# breakout4hold.net
KiCad netlist of a schematic drawn in EAGLE
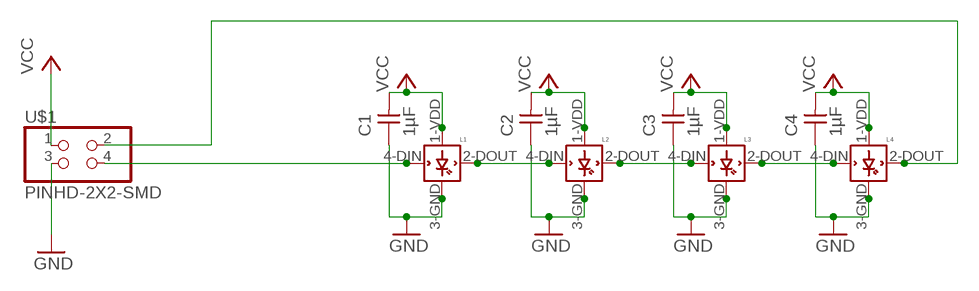
[diagram p0: schematic, sheet 1]

(export (version "E")
  (design (tool "Eeschema 10.0.6"))
  (components
    (comp (ref "C1")
      (value "1µF")
      (footprint "eagle-import:C1206FAB")
      (libsource (lib "eagle-import") (part "CAP-UNPOLARIZEDFAB"))
    )
    (comp (ref "C2")
      (value "1µF")
      (footprint "eagle-import:C1206FAB")
      (libsource (lib "eagle-import") (part "CAP-UNPOLARIZEDFAB"))
    )
    (comp (ref "C3")
      (value "1µF")
      (footprint "eagle-import:C1206FAB")
      (libsource (lib "eagle-import") (part "CAP-UNPOLARIZEDFAB"))
    )
    (comp (ref "C4")
      (value "1µF")
      (footprint "eagle-import:C1206FAB")
      (libsource (lib "eagle-import") (part "CAP-UNPOLARIZEDFAB"))
    )
    (comp (ref "L1")
      (value "WS2812B")
      (footprint "eagle-import:WS2812B")
      (libsource (lib "eagle-import") (part "WS2812B"))
    )
    (comp (ref "L2")
      (value "WS2812B")
      (footprint "eagle-import:WS2812B")
      (libsource (lib "eagle-import") (part "WS2812B"))
    )
    (comp (ref "L3")
      (value "WS2812B")
      (footprint "eagle-import:WS2812B")
      (libsource (lib "eagle-import") (part "WS2812B"))
    )
    (comp (ref "L4")
      (value "WS2812B")
      (footprint "eagle-import:WS2812B")
      (libsource (lib "eagle-import") (part "WS2812B"))
    )
    (comp (ref "U$1")
      (value "PINHD-2X2-SMD")
      (footprint "eagle-import:2X02SMD")
      (libsource (lib "eagle-import") (part "PINHD-2X2-SMD"))
    )
  )
  (nets
    (net (code "1") (name "GND") (class "Default")
      (node (ref "C1") (pin "1") (pinfunction "1_1") (pintype "passive"))
      (node (ref "C2") (pin "1") (pinfunction "1_1") (pintype "passive"))
      (node (ref "C3") (pin "1") (pinfunction "1_1") (pintype "passive"))
      (node (ref "C4") (pin "1") (pinfunction "1_1") (pintype "passive"))
      (node (ref "L1") (pin "3-GND") (pinfunction "GND_3-GND") (pintype "bidirectional"))
      (node (ref "L2") (pin "3-GND") (pinfunction "GND_3-GND") (pintype "bidirectional"))
      (node (ref "L3") (pin "3-GND") (pinfunction "GND_3-GND") (pintype "bidirectional"))
      (node (ref "L4") (pin "3-GND") (pinfunction "GND_3-GND") (pintype "bidirectional"))
      (node (ref "U$1") (pin "3") (pinfunction "3_3") (pintype "passive"))
    )
    (net (code "2") (name "Net-(L1-DIN)") (class "Default")
      (node (ref "L1") (pin "4-DIN") (pinfunction "DIN_4-DIN") (pintype "input"))
      (node (ref "U$1") (pin "4") (pinfunction "4_4") (pintype "passive"))
    )
    (net (code "3") (name "Net-(L1-DOUT)") (class "Default")
      (node (ref "L1") (pin "2-DOUT") (pinfunction "DOUT_2-DOUT") (pintype "output"))
      (node (ref "L2") (pin "4-DIN") (pinfunction "DIN_4-DIN") (pintype "input"))
    )
    (net (code "4") (name "Net-(L2-DOUT)") (class "Default")
      (node (ref "L2") (pin "2-DOUT") (pinfunction "DOUT_2-DOUT") (pintype "output"))
      (node (ref "L3") (pin "4-DIN") (pinfunction "DIN_4-DIN") (pintype "input"))
    )
    (net (code "5") (name "Net-(L3-DOUT)") (class "Default")
      (node (ref "L3") (pin "2-DOUT") (pinfunction "DOUT_2-DOUT") (pintype "output"))
      (node (ref "L4") (pin "4-DIN") (pinfunction "DIN_4-DIN") (pintype "input"))
    )
    (net (code "6") (name "Net-(L4-DOUT)") (class "Default")
      (node (ref "L4") (pin "2-DOUT") (pinfunction "DOUT_2-DOUT") (pintype "output"))
      (node (ref "U$1") (pin "2") (pinfunction "2_2") (pintype "passive"))
    )
    (net (code "7") (name "VCC") (class "Default")
      (node (ref "C1") (pin "2") (pinfunction "2_2") (pintype "passive"))
      (node (ref "C2") (pin "2") (pinfunction "2_2") (pintype "passive"))
      (node (ref "C3") (pin "2") (pinfunction "2_2") (pintype "passive"))
      (node (ref "C4") (pin "2") (pinfunction "2_2") (pintype "passive"))
      (node (ref "L1") (pin "1-VDD") (pinfunction "VDD_1-VDD") (pintype "bidirectional"))
      (node (ref "L2") (pin "1-VDD") (pinfunction "VDD_1-VDD") (pintype "bidirectional"))
      (node (ref "L3") (pin "1-VDD") (pinfunction "VDD_1-VDD") (pintype "bidirectional"))
      (node (ref "L4") (pin "1-VDD") (pinfunction "VDD_1-VDD") (pintype "bidirectional"))
      (node (ref "U$1") (pin "1") (pinfunction "1_1") (pintype "passive"))
    )
  )
)
